# PCB_Timbangan.net
KiCad netlist of a schematic drawn in EasyEDA
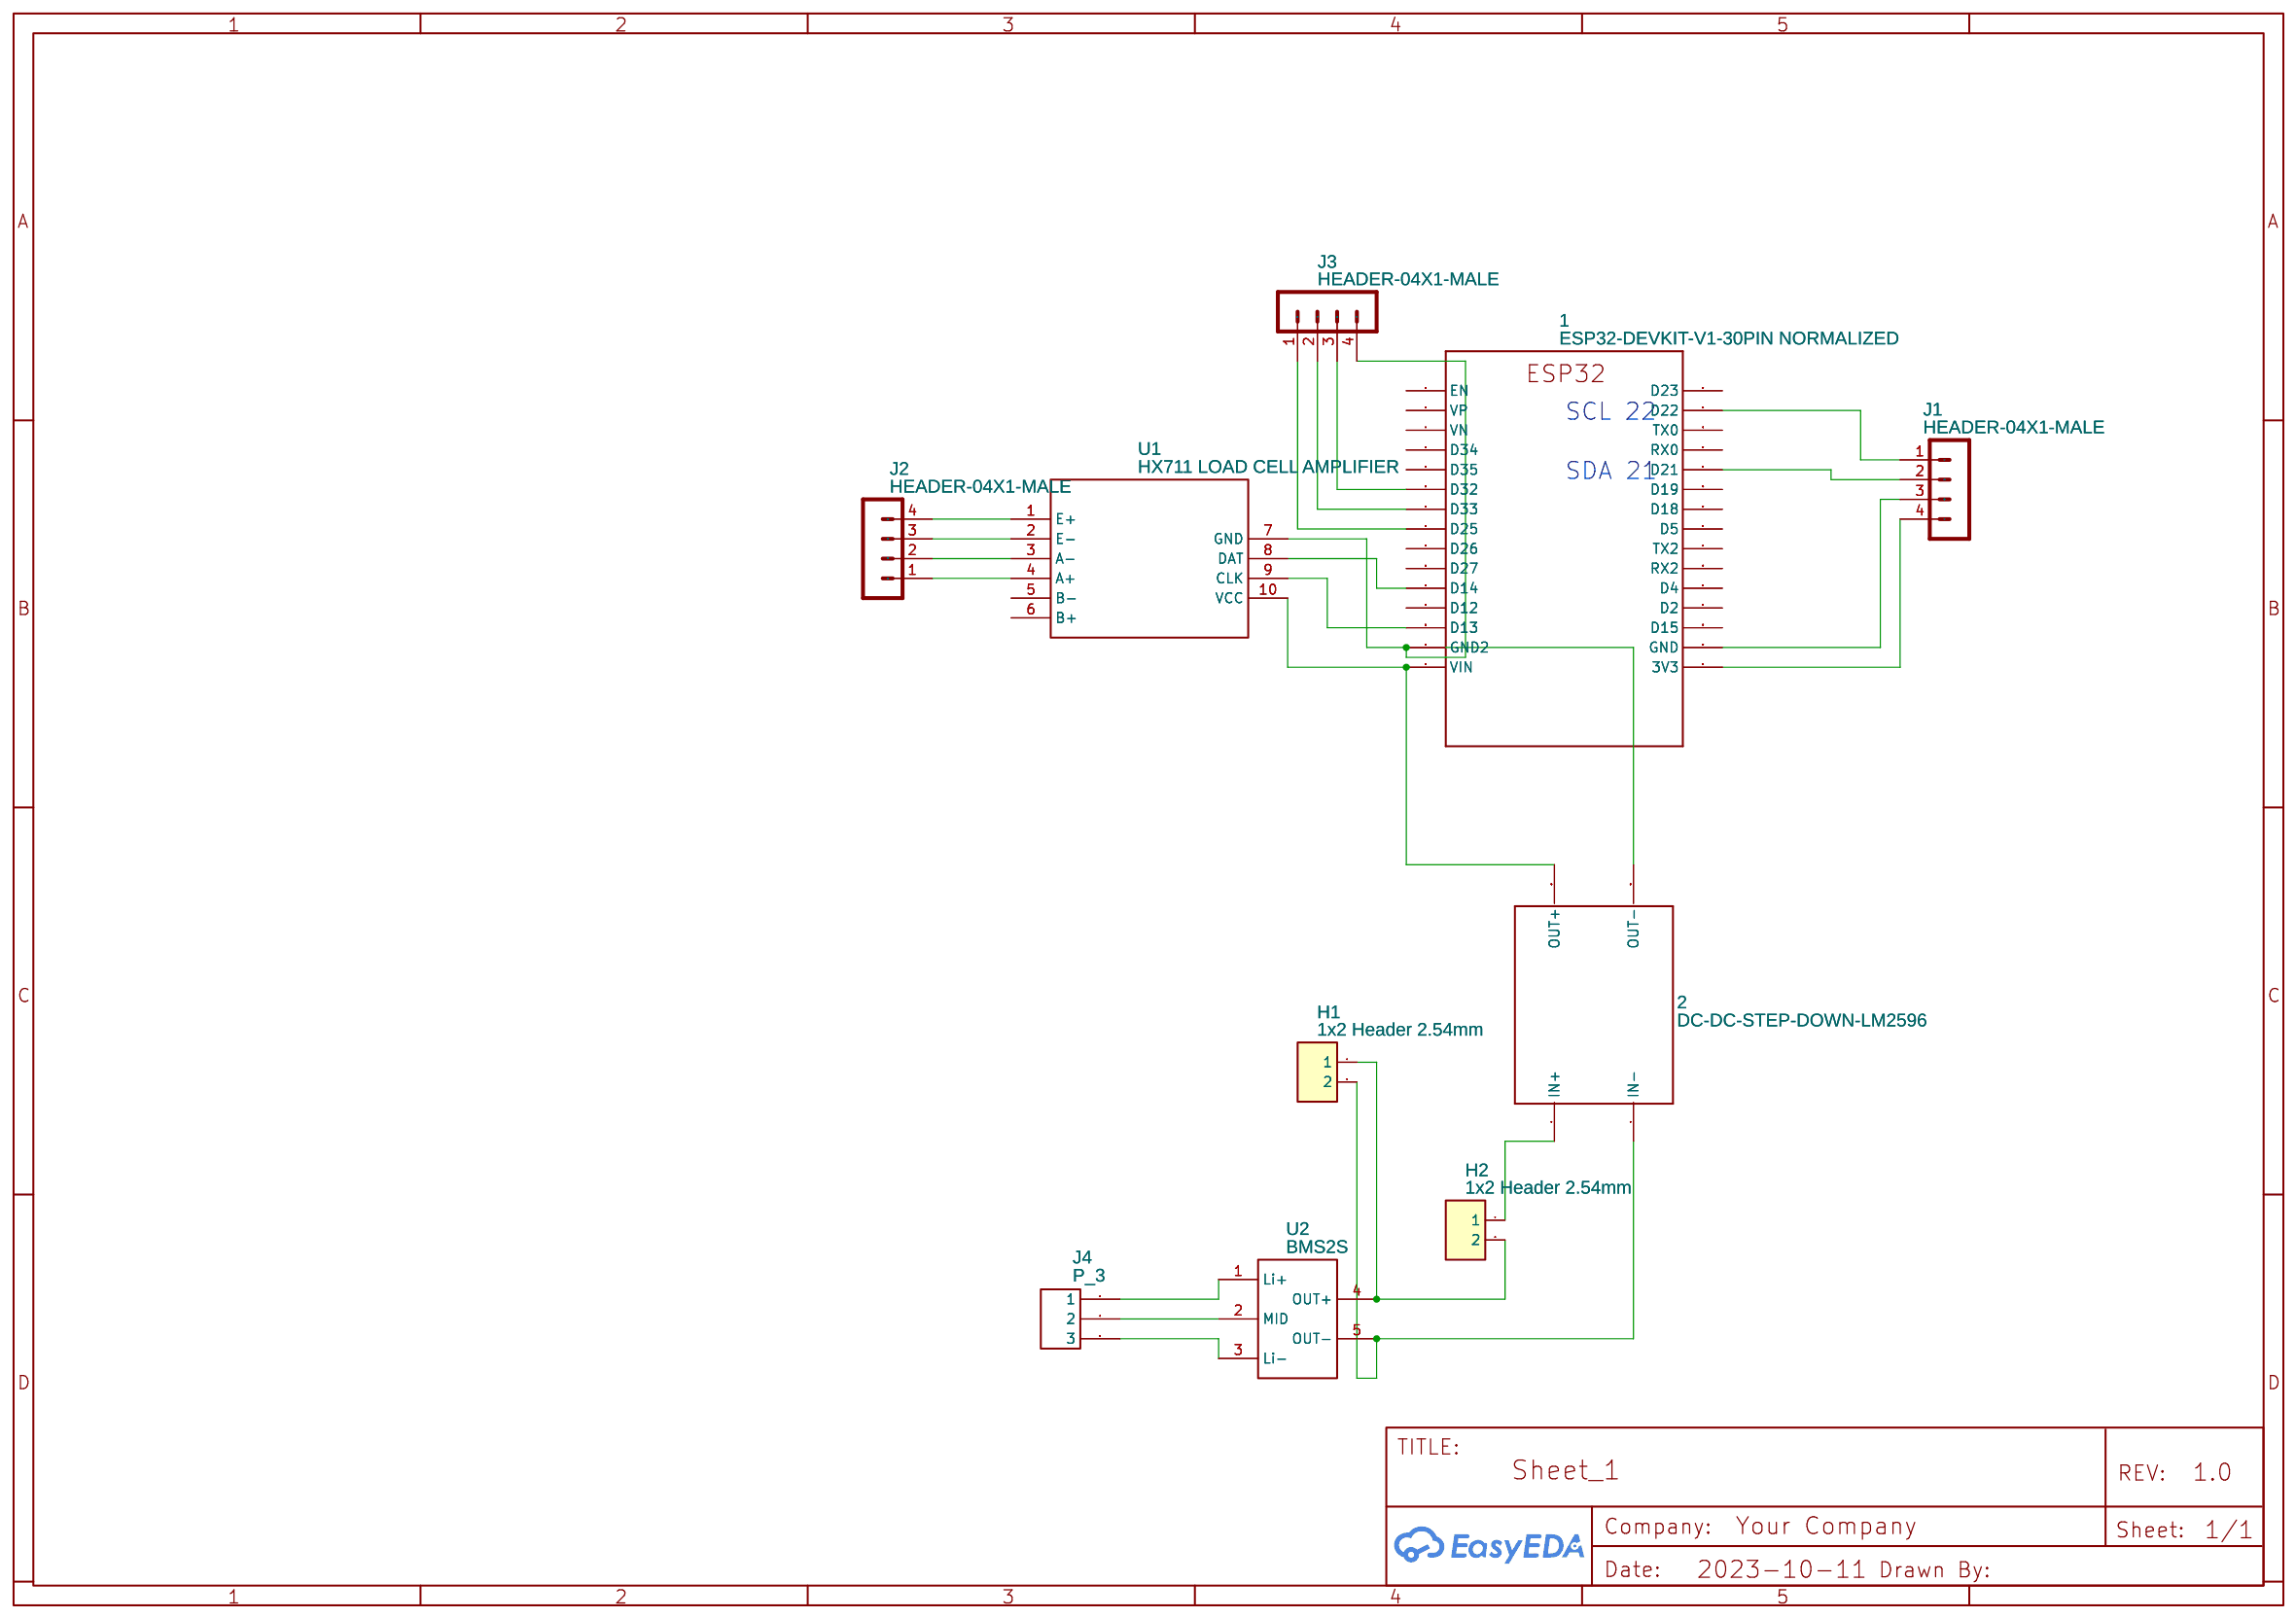
[diagram p0: schematic sheet]

(export (version "E")
  (design (tool "Eeschema 10.0.6"))
  (components
    (comp (ref "1")
      (value "ESP32-DEVKIT-V1-30PIN NORMALIZED")
      (libsource (lib "") (part "ESP32-DEVKIT-V1-30PIN"))
    )
    (comp (ref "2") (value "DC-DC-STEP-DOWN-LM2596") (libsource (lib "") (part "DC-DC-STEP-DOWN-LM2596")))
    (comp (ref "H1")
      (value "1x2 Header 2.54mm")
      (fields (field (name "Manufacturer Part") "New SchematicLib"))
      (libsource (lib "") (part "1x2 Header 2.54mm"))
    )
    (comp (ref "H2")
      (value "1x2 Header 2.54mm")
      (fields (field (name "Manufacturer Part") "New SchematicLib"))
      (libsource (lib "") (part "1x2 Header 2.54mm"))
    )
    (comp (ref "J1") (value "HEADER-04X1-MALE") (libsource (lib "") (part "HEADER-04X1-MALE_1")))
    (comp (ref "J2") (value "HEADER-04X1-MALE") (libsource (lib "") (part "HEADER-04X1-MALE")))
    (comp (ref "J3") (value "HEADER-04X1-MALE") (libsource (lib "") (part "HEADER-04X1-MALE_2")))
    (comp (ref "J4") (value "P_3") (libsource (lib "") (part "P_3")))
    (comp (ref "U1")
      (value "HX711 LOAD CELL AMPLIFIER")
      (libsource (lib "") (part "HX711 LOAD CELL AMPLIFIER"))
    )
    (comp (ref "U2") (value "BMS2S") (libsource (lib "") (part "BMS2S")))
  )
  (nets
    (net (code "1") (name "Net-(1-Pad3V3)") (class "Default")
      (node (ref "1") (pin "3V3") (pinfunction "3V3_3V3") (pintype "unspecified"))
      (node (ref "J1") (pin "4") (pinfunction "4_4") (pintype "unspecified"))
    )
    (net (code "2") (name "Net-(1-PadD21)") (class "Default")
      (node (ref "1") (pin "D21") (pinfunction "D21_D21") (pintype "unspecified"))
      (node (ref "J1") (pin "2") (pinfunction "2_2") (pintype "unspecified"))
    )
    (net (code "3") (name "Net-(1-PadD22)") (class "Default")
      (node (ref "1") (pin "D22") (pinfunction "D22_D22") (pintype "unspecified"))
      (node (ref "J1") (pin "1") (pinfunction "1_1") (pintype "unspecified"))
    )
    (net (code "4") (name "Net-(1-PadD25)") (class "Default")
      (node (ref "1") (pin "D25") (pinfunction "D25_D25") (pintype "unspecified"))
      (node (ref "J3") (pin "1") (pinfunction "1_1") (pintype "unspecified"))
    )
    (net (code "5") (name "Net-(1-PadD32)") (class "Default")
      (node (ref "1") (pin "D32") (pinfunction "D32_D32") (pintype "unspecified"))
      (node (ref "J3") (pin "3") (pinfunction "3_3") (pintype "unspecified"))
    )
    (net (code "6") (name "Net-(1-PadD33)") (class "Default")
      (node (ref "1") (pin "D33") (pinfunction "D33_D33") (pintype "unspecified"))
      (node (ref "J3") (pin "2") (pinfunction "2_2") (pintype "unspecified"))
    )
    (net (code "7") (name "Net-(1-PadGND)") (class "Default")
      (node (ref "1") (pin "GND") (pinfunction "GND_GND") (pintype "unspecified"))
      (node (ref "J1") (pin "3") (pinfunction "3_3") (pintype "unspecified"))
    )
    (net (code "8") (name "Net-(2-PadIN+)") (class "Default")
      (node (ref "2") (pin "IN+") (pinfunction "IN+_IN+") (pintype "bidirectional"))
      (node (ref "H2") (pin "1") (pinfunction "1_1") (pintype "unspecified"))
    )
    (net (code "9") (name "Net-(U1-A+)") (class "Default")
      (node (ref "J2") (pin "1") (pinfunction "1_1") (pintype "unspecified"))
      (node (ref "U1") (pin "4") (pinfunction "A+_4") (pintype "unspecified"))
    )
    (net (code "10") (name "Net-(U1-A-)") (class "Default")
      (node (ref "J2") (pin "2") (pinfunction "2_2") (pintype "unspecified"))
      (node (ref "U1") (pin "3") (pinfunction "A-_3") (pintype "unspecified"))
    )
    (net (code "11") (name "Net-(U1-CLK)") (class "Default")
      (node (ref "1") (pin "D13") (pinfunction "D13_D13") (pintype "unspecified"))
      (node (ref "U1") (pin "9") (pinfunction "CLK_9") (pintype "unspecified"))
    )
    (net (code "12") (name "Net-(U1-DAT)") (class "Default")
      (node (ref "1") (pin "D14") (pinfunction "D14_D14") (pintype "unspecified"))
      (node (ref "U1") (pin "8") (pinfunction "DAT_8") (pintype "unspecified"))
    )
    (net (code "13") (name "Net-(U1-E+)") (class "Default")
      (node (ref "J2") (pin "4") (pinfunction "4_4") (pintype "unspecified"))
      (node (ref "U1") (pin "1") (pinfunction "E+_1") (pintype "unspecified"))
    )
    (net (code "14") (name "Net-(U1-E-)") (class "Default")
      (node (ref "J2") (pin "3") (pinfunction "3_3") (pintype "unspecified"))
      (node (ref "U1") (pin "2") (pinfunction "E-_2") (pintype "unspecified"))
    )
    (net (code "15") (name "Net-(U1-GND)") (class "Default")
      (node (ref "1") (pin "GND2") (pinfunction "GND2_GND2") (pintype "unspecified"))
      (node (ref "2") (pin "OUT-") (pinfunction "OUT-_OUT-") (pintype "bidirectional"))
      (node (ref "J3") (pin "4") (pinfunction "4_4") (pintype "unspecified"))
      (node (ref "U1") (pin "7") (pinfunction "GND_7") (pintype "unspecified"))
    )
    (net (code "16") (name "Net-(U1-VCC)") (class "Default")
      (node (ref "1") (pin "VIN") (pinfunction "VIN_VIN") (pintype "unspecified"))
      (node (ref "2") (pin "OUT+") (pinfunction "OUT+_OUT+") (pintype "bidirectional"))
      (node (ref "U1") (pin "10") (pinfunction "VCC_10") (pintype "unspecified"))
    )
    (net (code "17") (name "Net-(U2-Li+)") (class "Default")
      (node (ref "J4") (pin "1") (pinfunction "1_1") (pintype "unspecified"))
      (node (ref "U2") (pin "1") (pinfunction "Li+_1") (pintype "unspecified"))
    )
    (net (code "18") (name "Net-(U2-Li-)") (class "Default")
      (node (ref "J4") (pin "3") (pinfunction "3_3") (pintype "unspecified"))
      (node (ref "U2") (pin "3") (pinfunction "Li-_3") (pintype "unspecified"))
    )
    (net (code "19") (name "Net-(U2-MID)") (class "Default")
      (node (ref "J4") (pin "2") (pinfunction "2_2") (pintype "unspecified"))
      (node (ref "U2") (pin "2") (pinfunction "MID_2") (pintype "unspecified"))
    )
    (net (code "20") (name "Net-(U2-OUT+)") (class "Default")
      (node (ref "H1") (pin "1") (pinfunction "1_1") (pintype "unspecified"))
      (node (ref "H2") (pin "2") (pinfunction "2_2") (pintype "unspecified"))
      (node (ref "U2") (pin "4") (pinfunction "OUT+_4") (pintype "unspecified"))
    )
    (net (code "21") (name "Net-(U2-OUT-)") (class "Default")
      (node (ref "2") (pin "IN-") (pinfunction "IN-_IN-") (pintype "bidirectional"))
      (node (ref "H1") (pin "2") (pinfunction "2_2") (pintype "unspecified"))
      (node (ref "U2") (pin "5") (pinfunction "OUT-_5") (pintype "unspecified"))
    )
    (net (code "22") (name "unconnected-(1-PadD2)") (class "Default")
      (node (ref "1") (pin "D2") (pinfunction "D2_D2") (pintype "unspecified"))
    )
    (net (code "23") (name "unconnected-(1-PadD4)") (class "Default")
      (node (ref "1") (pin "D4") (pinfunction "D4_D4") (pintype "unspecified"))
    )
    (net (code "24") (name "unconnected-(1-PadD5)") (class "Default")
      (node (ref "1") (pin "D5") (pinfunction "D5_D5") (pintype "unspecified"))
    )
    (net (code "25") (name "unconnected-(1-PadD12)") (class "Default")
      (node (ref "1") (pin "D12") (pinfunction "D12_D12") (pintype "unspecified"))
    )
    (net (code "26") (name "unconnected-(1-PadD15)") (class "Default")
      (node (ref "1") (pin "D15") (pinfunction "D15_D15") (pintype "unspecified"))
    )
    (net (code "27") (name "unconnected-(1-PadD18)") (class "Default")
      (node (ref "1") (pin "D18") (pinfunction "D18_D18") (pintype "unspecified"))
    )
    (net (code "28") (name "unconnected-(1-PadD19)") (class "Default")
      (node (ref "1") (pin "D19") (pinfunction "D19_D19") (pintype "unspecified"))
    )
    (net (code "29") (name "unconnected-(1-PadD23)") (class "Default")
      (node (ref "1") (pin "D23") (pinfunction "D23_D23") (pintype "unspecified"))
    )
    (net (code "30") (name "unconnected-(1-PadD26)") (class "Default")
      (node (ref "1") (pin "D26") (pinfunction "D26_D26") (pintype "unspecified"))
    )
    (net (code "31") (name "unconnected-(1-PadD27)") (class "Default")
      (node (ref "1") (pin "D27") (pinfunction "D27_D27") (pintype "unspecified"))
    )
    (net (code "32") (name "unconnected-(1-PadD34)") (class "Default")
      (node (ref "1") (pin "D34") (pinfunction "D34_D34") (pintype "unspecified"))
    )
    (net (code "33") (name "unconnected-(1-PadD35)") (class "Default")
      (node (ref "1") (pin "D35") (pinfunction "D35_D35") (pintype "unspecified"))
    )
    (net (code "34") (name "unconnected-(1-PadEN)") (class "Default")
      (node (ref "1") (pin "EN") (pinfunction "EN_EN") (pintype "unspecified"))
    )
    (net (code "35") (name "unconnected-(1-PadRX0)") (class "Default")
      (node (ref "1") (pin "RX0") (pinfunction "RX0_RX0") (pintype "unspecified"))
    )
    (net (code "36") (name "unconnected-(1-PadRX2)") (class "Default")
      (node (ref "1") (pin "RX2") (pinfunction "RX2_RX2") (pintype "unspecified"))
    )
    (net (code "37") (name "unconnected-(1-PadTX0)") (class "Default")
      (node (ref "1") (pin "TX0") (pinfunction "TX0_TX0") (pintype "unspecified"))
    )
    (net (code "38") (name "unconnected-(1-PadTX2)") (class "Default")
      (node (ref "1") (pin "TX2") (pinfunction "TX2_TX2") (pintype "unspecified"))
    )
    (net (code "39") (name "unconnected-(1-PadVN)") (class "Default")
      (node (ref "1") (pin "VN") (pinfunction "VN_VN") (pintype "unspecified"))
    )
    (net (code "40") (name "unconnected-(1-PadVP)") (class "Default")
      (node (ref "1") (pin "VP") (pinfunction "VP_VP") (pintype "unspecified"))
    )
    (net (code "41") (name "unconnected-(U1-B+-Pad6)") (class "Default")
      (node (ref "U1") (pin "6") (pinfunction "B+_6") (pintype "unspecified"))
    )
    (net (code "42") (name "unconnected-(U1-B--Pad5)") (class "Default")
      (node (ref "U1") (pin "5") (pinfunction "B-_5") (pintype "unspecified"))
    )
  )
)
